# I2CRJ45X8.net
KiCad netlist of a schematic drawn in EAGLE
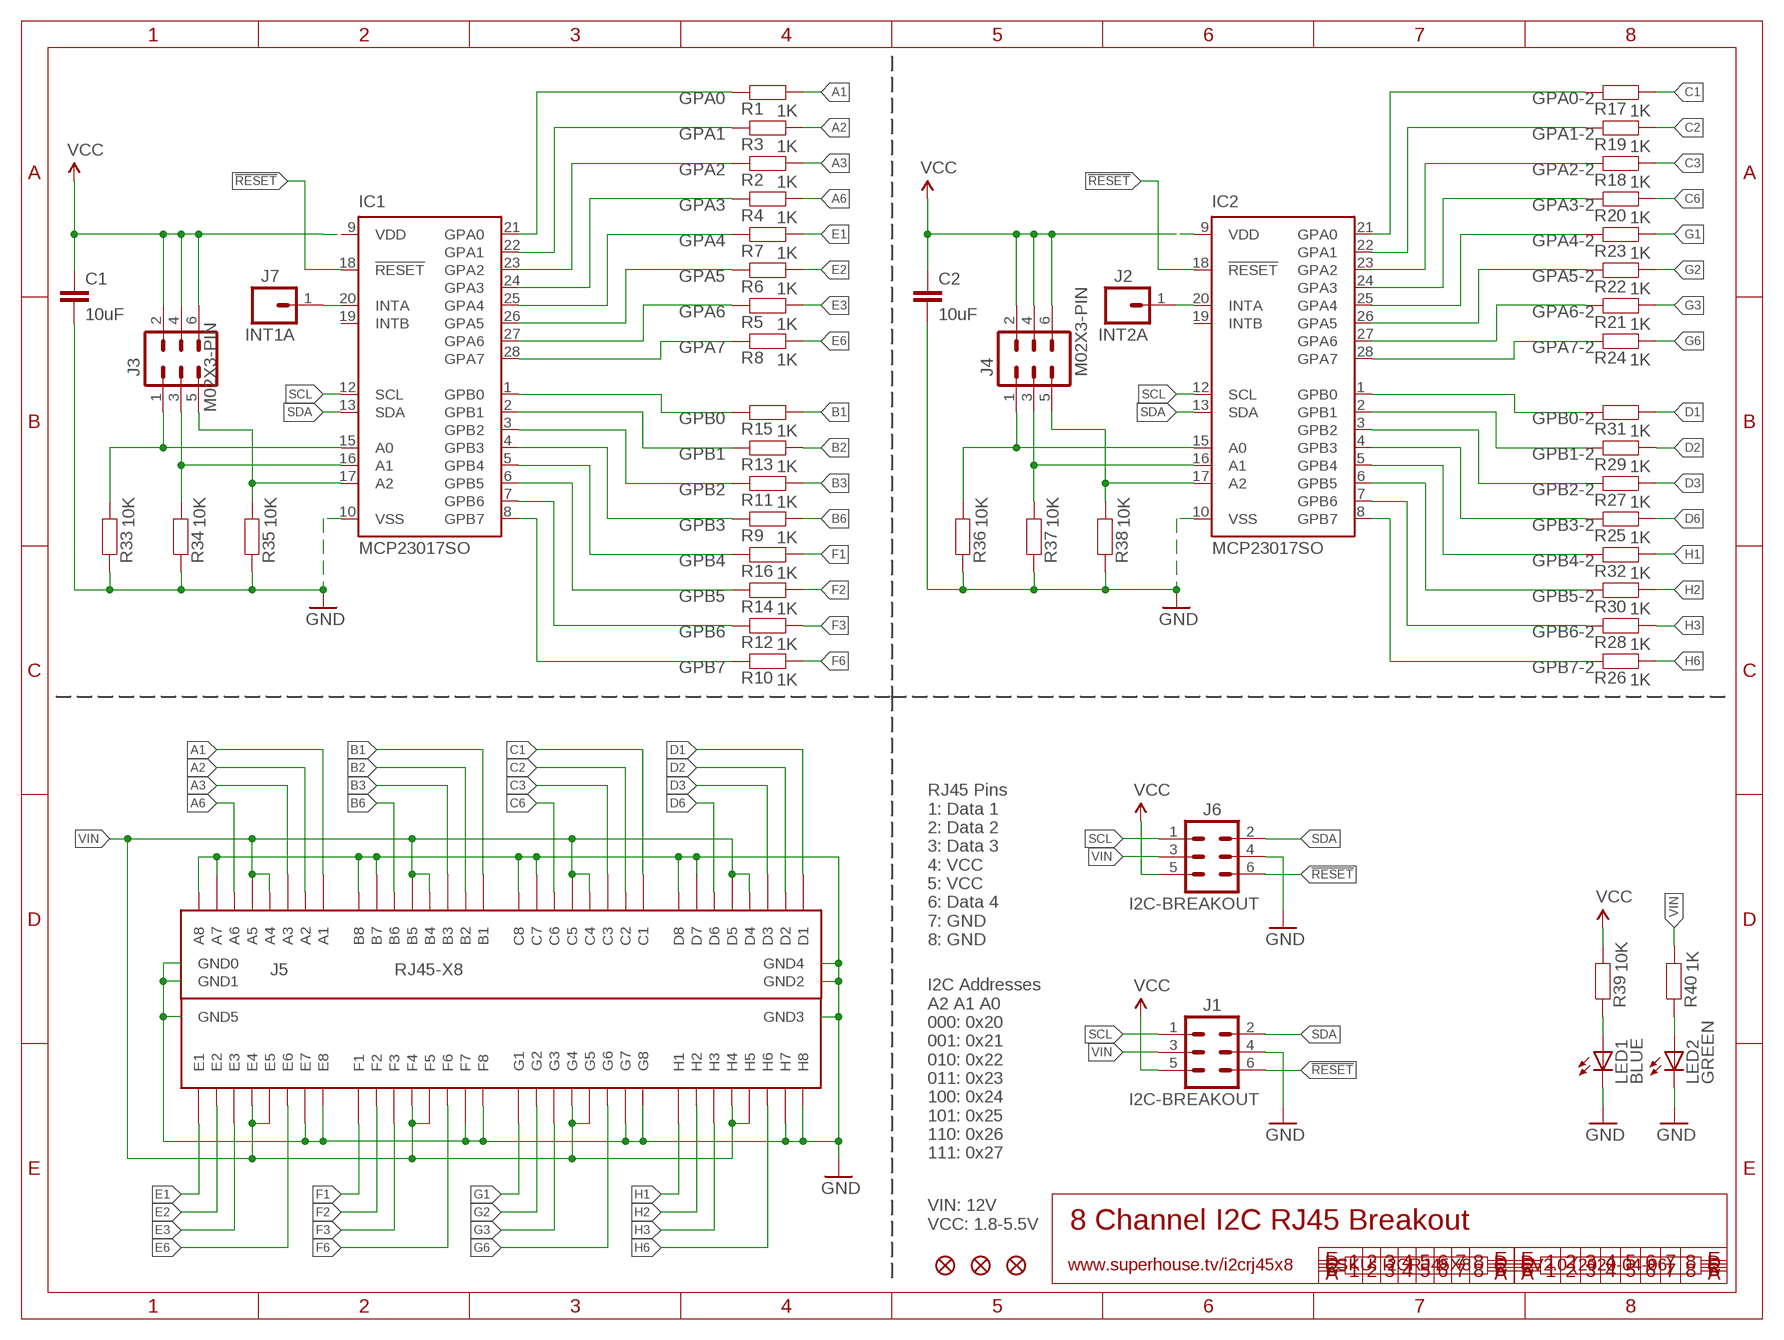
[diagram p0: schematic, sheet 1]

(export (version "E")
  (design (tool "Eeschema 10.0.6"))
  (components
    (comp (ref "C1")
      (value "10uF")
      (footprint "eagle-import:C0805")
      (libsource (lib "eagle-import") (part "CAP0805"))
    )
    (comp (ref "C2")
      (value "10uF")
      (footprint "eagle-import:C0805")
      (libsource (lib "eagle-import") (part "CAP0805"))
    )
    (comp (ref "FID1")
      (value "FIDUCIAL1X2.5")
      (footprint "eagle-import:FIDUCIAL-1X2.5")
      (libsource (lib "eagle-import") (part "FIDUCIAL1X2.5"))
    )
    (comp (ref "FID2")
      (value "FIDUCIAL1X2.5")
      (footprint "eagle-import:FIDUCIAL-1X2.5")
      (libsource (lib "eagle-import") (part "FIDUCIAL1X2.5"))
    )
    (comp (ref "FID3")
      (value "FIDUCIAL1X2.5")
      (footprint "eagle-import:FIDUCIAL-1X2.5")
      (libsource (lib "eagle-import") (part "FIDUCIAL1X2.5"))
    )
    (comp (ref "IC1")
      (value "MCP23017SO")
      (footprint "eagle-import:SO28W")
      (libsource (lib "eagle-import") (part "MCP23017SO"))
    )
    (comp (ref "IC2")
      (value "MCP23017SO")
      (footprint "eagle-import:SO28W")
      (libsource (lib "eagle-import") (part "MCP23017SO"))
    )
    (comp (ref "J1")
      (value "I2C-BREAKOUT")
      (footprint "eagle-import:2X03-SHROUDED")
      (libsource (lib "eagle-import") (part "M02X3-SHROUDED"))
    )
    (comp (ref "J2")
      (value "INT2A")
      (footprint "eagle-import:1X01")
      (libsource (lib "eagle-import") (part "M01-PLAIN"))
    )
    (comp (ref "J3")
      (value "M02X3-PIN")
      (footprint "eagle-import:2X03-P")
      (libsource (lib "eagle-import") (part "M02X3-PIN"))
    )
    (comp (ref "J4")
      (value "M02X3-PIN")
      (footprint "eagle-import:2X03-P")
      (libsource (lib "eagle-import") (part "M02X3-PIN"))
    )
    (comp (ref "J5")
      (value "RJ45-X8")
      (footprint "eagle-import:RJ45-2X4")
      (libsource (lib "eagle-import") (part "RJ45-X8"))
    )
    (comp (ref "J6")
      (value "I2C-BREAKOUT")
      (footprint "eagle-import:2X03-SHROUDED")
      (libsource (lib "eagle-import") (part "M02X3-SHROUDED"))
    )
    (comp (ref "J7")
      (value "INT1A")
      (footprint "eagle-import:1X01")
      (libsource (lib "eagle-import") (part "M01-PLAIN"))
    )
    (comp (ref "LED1")
      (value "BLUE")
      (footprint "eagle-import:LED-0603")
      (libsource (lib "eagle-import") (part "LED0603"))
    )
    (comp (ref "LED2")
      (value "GREEN")
      (footprint "eagle-import:LED-0603")
      (libsource (lib "eagle-import") (part "LED0603"))
    )
    (comp (ref "R1")
      (value "1K")
      (footprint "eagle-import:R0603")
      (libsource (lib "eagle-import") (part "RESISTOR0603"))
    )
    (comp (ref "R2")
      (value "1K")
      (footprint "eagle-import:R0603")
      (libsource (lib "eagle-import") (part "RESISTOR0603"))
    )
    (comp (ref "R3")
      (value "1K")
      (footprint "eagle-import:R0603")
      (libsource (lib "eagle-import") (part "RESISTOR0603"))
    )
    (comp (ref "R4")
      (value "1K")
      (footprint "eagle-import:R0603")
      (libsource (lib "eagle-import") (part "RESISTOR0603"))
    )
    (comp (ref "R5")
      (value "1K")
      (footprint "eagle-import:R0603")
      (libsource (lib "eagle-import") (part "RESISTOR0603"))
    )
    (comp (ref "R6")
      (value "1K")
      (footprint "eagle-import:R0603")
      (libsource (lib "eagle-import") (part "RESISTOR0603"))
    )
    (comp (ref "R7")
      (value "1K")
      (footprint "eagle-import:R0603")
      (libsource (lib "eagle-import") (part "RESISTOR0603"))
    )
    (comp (ref "R8")
      (value "1K")
      (footprint "eagle-import:R0603")
      (libsource (lib "eagle-import") (part "RESISTOR0603"))
    )
    (comp (ref "R9")
      (value "1K")
      (footprint "eagle-import:R0603")
      (libsource (lib "eagle-import") (part "RESISTOR0603"))
    )
    (comp (ref "R10")
      (value "1K")
      (footprint "eagle-import:R0603")
      (libsource (lib "eagle-import") (part "RESISTOR0603"))
    )
    (comp (ref "R11")
      (value "1K")
      (footprint "eagle-import:R0603")
      (libsource (lib "eagle-import") (part "RESISTOR0603"))
    )
    (comp (ref "R12")
      (value "1K")
      (footprint "eagle-import:R0603")
      (libsource (lib "eagle-import") (part "RESISTOR0603"))
    )
    (comp (ref "R13")
      (value "1K")
      (footprint "eagle-import:R0603")
      (libsource (lib "eagle-import") (part "RESISTOR0603"))
    )
    (comp (ref "R14")
      (value "1K")
      (footprint "eagle-import:R0603")
      (libsource (lib "eagle-import") (part "RESISTOR0603"))
    )
    (comp (ref "R15")
      (value "1K")
      (footprint "eagle-import:R0603")
      (libsource (lib "eagle-import") (part "RESISTOR0603"))
    )
    (comp (ref "R16")
      (value "1K")
      (footprint "eagle-import:R0603")
      (libsource (lib "eagle-import") (part "RESISTOR0603"))
    )
    (comp (ref "R17")
      (value "1K")
      (footprint "eagle-import:R0603")
      (libsource (lib "eagle-import") (part "RESISTOR0603"))
    )
    (comp (ref "R18")
      (value "1K")
      (footprint "eagle-import:R0603")
      (libsource (lib "eagle-import") (part "RESISTOR0603"))
    )
    (comp (ref "R19")
      (value "1K")
      (footprint "eagle-import:R0603")
      (libsource (lib "eagle-import") (part "RESISTOR0603"))
    )
    (comp (ref "R20")
      (value "1K")
      (footprint "eagle-import:R0603")
      (libsource (lib "eagle-import") (part "RESISTOR0603"))
    )
    (comp (ref "R21")
      (value "1K")
      (footprint "eagle-import:R0603")
      (libsource (lib "eagle-import") (part "RESISTOR0603"))
    )
    (comp (ref "R22")
      (value "1K")
      (footprint "eagle-import:R0603")
      (libsource (lib "eagle-import") (part "RESISTOR0603"))
    )
    (comp (ref "R23")
      (value "1K")
      (footprint "eagle-import:R0603")
      (libsource (lib "eagle-import") (part "RESISTOR0603"))
    )
    (comp (ref "R24")
      (value "1K")
      (footprint "eagle-import:R0603")
      (libsource (lib "eagle-import") (part "RESISTOR0603"))
    )
    (comp (ref "R25")
      (value "1K")
      (footprint "eagle-import:R0603")
      (libsource (lib "eagle-import") (part "RESISTOR0603"))
    )
    (comp (ref "R26")
      (value "1K")
      (footprint "eagle-import:R0603")
      (libsource (lib "eagle-import") (part "RESISTOR0603"))
    )
    (comp (ref "R27")
      (value "1K")
      (footprint "eagle-import:R0603")
      (libsource (lib "eagle-import") (part "RESISTOR0603"))
    )
    (comp (ref "R28")
      (value "1K")
      (footprint "eagle-import:R0603")
      (libsource (lib "eagle-import") (part "RESISTOR0603"))
    )
    (comp (ref "R29")
      (value "1K")
      (footprint "eagle-import:R0603")
      (libsource (lib "eagle-import") (part "RESISTOR0603"))
    )
    (comp (ref "R30")
      (value "1K")
      (footprint "eagle-import:R0603")
      (libsource (lib "eagle-import") (part "RESISTOR0603"))
    )
    (comp (ref "R31")
      (value "1K")
      (footprint "eagle-import:R0603")
      (libsource (lib "eagle-import") (part "RESISTOR0603"))
    )
    (comp (ref "R32")
      (value "1K")
      (footprint "eagle-import:R0603")
      (libsource (lib "eagle-import") (part "RESISTOR0603"))
    )
    (comp (ref "R33")
      (value "10K")
      (footprint "eagle-import:R0603")
      (libsource (lib "eagle-import") (part "RESISTOR0603"))
    )
    (comp (ref "R34")
      (value "10K")
      (footprint "eagle-import:R0603")
      (libsource (lib "eagle-import") (part "RESISTOR0603"))
    )
    (comp (ref "R35")
      (value "10K")
      (footprint "eagle-import:R0603")
      (libsource (lib "eagle-import") (part "RESISTOR0603"))
    )
    (comp (ref "R36")
      (value "10K")
      (footprint "eagle-import:R0603")
      (libsource (lib "eagle-import") (part "RESISTOR0603"))
    )
    (comp (ref "R37")
      (value "10K")
      (footprint "eagle-import:R0603")
      (libsource (lib "eagle-import") (part "RESISTOR0603"))
    )
    (comp (ref "R38")
      (value "10K")
      (footprint "eagle-import:R0603")
      (libsource (lib "eagle-import") (part "RESISTOR0603"))
    )
    (comp (ref "R39")
      (value "10K")
      (footprint "eagle-import:R0603")
      (libsource (lib "eagle-import") (part "RESISTOR0603"))
    )
    (comp (ref "R40")
      (value "1K")
      (footprint "eagle-import:R0603")
      (libsource (lib "eagle-import") (part "RESISTOR0603"))
    )
  )
  (nets
    (net (code "1") (name "/GPA0") (class "Default")
      (node (ref "IC1") (pin "21") (pinfunction "GPA0_21") (pintype "bidirectional"))
      (node (ref "R1") (pin "1") (pinfunction "1_1") (pintype "passive"))
    )
    (net (code "2") (name "/GPA0-2") (class "Default")
      (node (ref "IC2") (pin "21") (pinfunction "GPA0_21") (pintype "bidirectional"))
      (node (ref "R17") (pin "1") (pinfunction "1_1") (pintype "passive"))
    )
    (net (code "3") (name "/GPA1") (class "Default")
      (node (ref "IC1") (pin "22") (pinfunction "GPA1_22") (pintype "bidirectional"))
      (node (ref "R3") (pin "1") (pinfunction "1_1") (pintype "passive"))
    )
    (net (code "4") (name "/GPA1-2") (class "Default")
      (node (ref "IC2") (pin "22") (pinfunction "GPA1_22") (pintype "bidirectional"))
      (node (ref "R19") (pin "1") (pinfunction "1_1") (pintype "passive"))
    )
    (net (code "5") (name "/GPA2") (class "Default")
      (node (ref "IC1") (pin "23") (pinfunction "GPA2_23") (pintype "bidirectional"))
      (node (ref "R2") (pin "1") (pinfunction "1_1") (pintype "passive"))
    )
    (net (code "6") (name "/GPA2-2") (class "Default")
      (node (ref "IC2") (pin "23") (pinfunction "GPA2_23") (pintype "bidirectional"))
      (node (ref "R18") (pin "1") (pinfunction "1_1") (pintype "passive"))
    )
    (net (code "7") (name "/GPA3") (class "Default")
      (node (ref "IC1") (pin "24") (pinfunction "GPA3_24") (pintype "bidirectional"))
      (node (ref "R4") (pin "1") (pinfunction "1_1") (pintype "passive"))
    )
    (net (code "8") (name "/GPA3-2") (class "Default")
      (node (ref "IC2") (pin "24") (pinfunction "GPA3_24") (pintype "bidirectional"))
      (node (ref "R20") (pin "1") (pinfunction "1_1") (pintype "passive"))
    )
    (net (code "9") (name "/GPA4") (class "Default")
      (node (ref "IC1") (pin "25") (pinfunction "GPA4_25") (pintype "bidirectional"))
      (node (ref "R7") (pin "1") (pinfunction "1_1") (pintype "passive"))
    )
    (net (code "10") (name "/GPA4-2") (class "Default")
      (node (ref "IC2") (pin "25") (pinfunction "GPA4_25") (pintype "bidirectional"))
      (node (ref "R23") (pin "1") (pinfunction "1_1") (pintype "passive"))
    )
    (net (code "11") (name "/GPA5") (class "Default")
      (node (ref "IC1") (pin "26") (pinfunction "GPA5_26") (pintype "bidirectional"))
      (node (ref "R6") (pin "1") (pinfunction "1_1") (pintype "passive"))
    )
    (net (code "12") (name "/GPA5-2") (class "Default")
      (node (ref "IC2") (pin "26") (pinfunction "GPA5_26") (pintype "bidirectional"))
      (node (ref "R22") (pin "1") (pinfunction "1_1") (pintype "passive"))
    )
    (net (code "13") (name "/GPA6") (class "Default")
      (node (ref "IC1") (pin "27") (pinfunction "GPA6_27") (pintype "bidirectional"))
      (node (ref "R5") (pin "1") (pinfunction "1_1") (pintype "passive"))
    )
    (net (code "14") (name "/GPA6-2") (class "Default")
      (node (ref "IC2") (pin "27") (pinfunction "GPA6_27") (pintype "bidirectional"))
      (node (ref "R21") (pin "1") (pinfunction "1_1") (pintype "passive"))
    )
    (net (code "15") (name "/GPA7") (class "Default")
      (node (ref "IC1") (pin "28") (pinfunction "GPA7_28") (pintype "bidirectional"))
      (node (ref "R8") (pin "1") (pinfunction "1_1") (pintype "passive"))
    )
    (net (code "16") (name "/GPA7-2") (class "Default")
      (node (ref "IC2") (pin "28") (pinfunction "GPA7_28") (pintype "bidirectional"))
      (node (ref "R24") (pin "1") (pinfunction "1_1") (pintype "passive"))
    )
    (net (code "17") (name "/GPB0") (class "Default")
      (node (ref "IC1") (pin "1") (pinfunction "GPB0_1") (pintype "bidirectional"))
      (node (ref "R15") (pin "1") (pinfunction "1_1") (pintype "passive"))
    )
    (net (code "18") (name "/GPB0-2") (class "Default")
      (node (ref "IC2") (pin "1") (pinfunction "GPB0_1") (pintype "bidirectional"))
      (node (ref "R31") (pin "1") (pinfunction "1_1") (pintype "passive"))
    )
    (net (code "19") (name "/GPB1") (class "Default")
      (node (ref "IC1") (pin "2") (pinfunction "GPB1_2") (pintype "bidirectional"))
      (node (ref "R13") (pin "1") (pinfunction "1_1") (pintype "passive"))
    )
    (net (code "20") (name "/GPB1-2") (class "Default")
      (node (ref "IC2") (pin "2") (pinfunction "GPB1_2") (pintype "bidirectional"))
      (node (ref "R29") (pin "1") (pinfunction "1_1") (pintype "passive"))
    )
    (net (code "21") (name "/GPB2") (class "Default")
      (node (ref "IC1") (pin "3") (pinfunction "GPB2_3") (pintype "bidirectional"))
      (node (ref "R11") (pin "1") (pinfunction "1_1") (pintype "passive"))
    )
    (net (code "22") (name "/GPB2-2") (class "Default")
      (node (ref "IC2") (pin "3") (pinfunction "GPB2_3") (pintype "bidirectional"))
      (node (ref "R27") (pin "1") (pinfunction "1_1") (pintype "passive"))
    )
    (net (code "23") (name "/GPB3") (class "Default")
      (node (ref "IC1") (pin "4") (pinfunction "GPB3_4") (pintype "bidirectional"))
      (node (ref "R9") (pin "1") (pinfunction "1_1") (pintype "passive"))
    )
    (net (code "24") (name "/GPB3-2") (class "Default")
      (node (ref "IC2") (pin "4") (pinfunction "GPB3_4") (pintype "bidirectional"))
      (node (ref "R25") (pin "1") (pinfunction "1_1") (pintype "passive"))
    )
    (net (code "25") (name "/GPB4") (class "Default")
      (node (ref "IC1") (pin "5") (pinfunction "GPB4_5") (pintype "bidirectional"))
      (node (ref "R16") (pin "1") (pinfunction "1_1") (pintype "passive"))
    )
    (net (code "26") (name "/GPB4-2") (class "Default")
      (node (ref "IC2") (pin "5") (pinfunction "GPB4_5") (pintype "bidirectional"))
      (node (ref "R32") (pin "1") (pinfunction "1_1") (pintype "passive"))
    )
    (net (code "27") (name "/GPB5") (class "Default")
      (node (ref "IC1") (pin "6") (pinfunction "GPB5_6") (pintype "bidirectional"))
      (node (ref "R14") (pin "1") (pinfunction "1_1") (pintype "passive"))
    )
    (net (code "28") (name "/GPB5-2") (class "Default")
      (node (ref "IC2") (pin "6") (pinfunction "GPB5_6") (pintype "bidirectional"))
      (node (ref "R30") (pin "1") (pinfunction "1_1") (pintype "passive"))
    )
    (net (code "29") (name "/GPB6") (class "Default")
      (node (ref "IC1") (pin "7") (pinfunction "GPB6_7") (pintype "bidirectional"))
      (node (ref "R12") (pin "1") (pinfunction "1_1") (pintype "passive"))
    )
    (net (code "30") (name "/GPB6-2") (class "Default")
      (node (ref "IC2") (pin "7") (pinfunction "GPB6_7") (pintype "bidirectional"))
      (node (ref "R28") (pin "1") (pinfunction "1_1") (pintype "passive"))
    )
    (net (code "31") (name "/GPB7") (class "Default")
      (node (ref "IC1") (pin "8") (pinfunction "GPB7_8") (pintype "bidirectional"))
      (node (ref "R10") (pin "1") (pinfunction "1_1") (pintype "passive"))
    )
    (net (code "32") (name "/GPB7-2") (class "Default")
      (node (ref "IC2") (pin "8") (pinfunction "GPB7_8") (pintype "bidirectional"))
      (node (ref "R26") (pin "1") (pinfunction "1_1") (pintype "passive"))
    )
    (net (code "33") (name "/~{RESET}") (class "Default")
      (node (ref "IC1") (pin "18") (pinfunction "~{RESET}_18") (pintype "input"))
      (node (ref "IC2") (pin "18") (pinfunction "~{RESET}_18") (pintype "input"))
      (node (ref "J1") (pin "6") (pinfunction "6_6") (pintype "passive"))
      (node (ref "J6") (pin "6") (pinfunction "6_6") (pintype "passive"))
    )
    (net (code "34") (name "A1") (class "Default")
      (node (ref "J5") (pin "A1") (pinfunction "A1_A1") (pintype "bidirectional"))
      (node (ref "R1") (pin "2") (pinfunction "2_2") (pintype "passive"))
    )
    (net (code "35") (name "A2") (class "Default")
      (node (ref "J5") (pin "A2") (pinfunction "A2_A2") (pintype "bidirectional"))
      (node (ref "R3") (pin "2") (pinfunction "2_2") (pintype "passive"))
    )
    (net (code "36") (name "A3") (class "Default")
      (node (ref "J5") (pin "A3") (pinfunction "A3_A3") (pintype "bidirectional"))
      (node (ref "R2") (pin "2") (pinfunction "2_2") (pintype "passive"))
    )
    (net (code "37") (name "A6") (class "Default")
      (node (ref "J5") (pin "A6") (pinfunction "A6_A6") (pintype "bidirectional"))
      (node (ref "R4") (pin "2") (pinfunction "2_2") (pintype "passive"))
    )
    (net (code "38") (name "B1") (class "Default")
      (node (ref "J5") (pin "B1") (pinfunction "B1_B1") (pintype "bidirectional"))
      (node (ref "R15") (pin "2") (pinfunction "2_2") (pintype "passive"))
    )
    (net (code "39") (name "B2") (class "Default")
      (node (ref "J5") (pin "B2") (pinfunction "B2_B2") (pintype "bidirectional"))
      (node (ref "R13") (pin "2") (pinfunction "2_2") (pintype "passive"))
    )
    (net (code "40") (name "B3") (class "Default")
      (node (ref "J5") (pin "B3") (pinfunction "B3_B3") (pintype "bidirectional"))
      (node (ref "R11") (pin "2") (pinfunction "2_2") (pintype "passive"))
    )
    (net (code "41") (name "B6") (class "Default")
      (node (ref "J5") (pin "B6") (pinfunction "B6_B6") (pintype "bidirectional"))
      (node (ref "R9") (pin "2") (pinfunction "2_2") (pintype "passive"))
    )
    (net (code "42") (name "C1") (class "Default")
      (node (ref "J5") (pin "C1") (pinfunction "C1_C1") (pintype "bidirectional"))
      (node (ref "R17") (pin "2") (pinfunction "2_2") (pintype "passive"))
    )
    (net (code "43") (name "C2") (class "Default")
      (node (ref "J5") (pin "C2") (pinfunction "C2_C2") (pintype "bidirectional"))
      (node (ref "R19") (pin "2") (pinfunction "2_2") (pintype "passive"))
    )
    (net (code "44") (name "C3") (class "Default")
      (node (ref "J5") (pin "C3") (pinfunction "C3_C3") (pintype "bidirectional"))
      (node (ref "R18") (pin "2") (pinfunction "2_2") (pintype "passive"))
    )
    (net (code "45") (name "C6") (class "Default")
      (node (ref "J5") (pin "C6") (pinfunction "C6_C6") (pintype "bidirectional"))
      (node (ref "R20") (pin "2") (pinfunction "2_2") (pintype "passive"))
    )
    (net (code "46") (name "D1") (class "Default")
      (node (ref "J5") (pin "D1") (pinfunction "D1_D1") (pintype "bidirectional"))
      (node (ref "R31") (pin "2") (pinfunction "2_2") (pintype "passive"))
    )
    (net (code "47") (name "D2") (class "Default")
      (node (ref "J5") (pin "D2") (pinfunction "D2_D2") (pintype "bidirectional"))
      (node (ref "R29") (pin "2") (pinfunction "2_2") (pintype "passive"))
    )
    (net (code "48") (name "D3") (class "Default")
      (node (ref "J5") (pin "D3") (pinfunction "D3_D3") (pintype "bidirectional"))
      (node (ref "R27") (pin "2") (pinfunction "2_2") (pintype "passive"))
    )
    (net (code "49") (name "D6") (class "Default")
      (node (ref "J5") (pin "D6") (pinfunction "D6_D6") (pintype "bidirectional"))
      (node (ref "R25") (pin "2") (pinfunction "2_2") (pintype "passive"))
    )
    (net (code "50") (name "E1") (class "Default")
      (node (ref "J5") (pin "E1") (pinfunction "E1_E1") (pintype "bidirectional"))
      (node (ref "R7") (pin "2") (pinfunction "2_2") (pintype "passive"))
    )
    (net (code "51") (name "E2") (class "Default")
      (node (ref "J5") (pin "E2") (pinfunction "E2_E2") (pintype "bidirectional"))
      (node (ref "R6") (pin "2") (pinfunction "2_2") (pintype "passive"))
    )
    (net (code "52") (name "E3") (class "Default")
      (node (ref "J5") (pin "E3") (pinfunction "E3_E3") (pintype "bidirectional"))
      (node (ref "R5") (pin "2") (pinfunction "2_2") (pintype "passive"))
    )
    (net (code "53") (name "E6") (class "Default")
      (node (ref "J5") (pin "E6") (pinfunction "E6_E6") (pintype "bidirectional"))
      (node (ref "R8") (pin "2") (pinfunction "2_2") (pintype "passive"))
    )
    (net (code "54") (name "F1") (class "Default")
      (node (ref "J5") (pin "F1") (pinfunction "F1_F1") (pintype "bidirectional"))
      (node (ref "R16") (pin "2") (pinfunction "2_2") (pintype "passive"))
    )
    (net (code "55") (name "F2") (class "Default")
      (node (ref "J5") (pin "F2") (pinfunction "F2_F2") (pintype "bidirectional"))
      (node (ref "R14") (pin "2") (pinfunction "2_2") (pintype "passive"))
    )
    (net (code "56") (name "F3") (class "Default")
      (node (ref "J5") (pin "F3") (pinfunction "F3_F3") (pintype "bidirectional"))
      (node (ref "R12") (pin "2") (pinfunction "2_2") (pintype "passive"))
    )
    (net (code "57") (name "F6") (class "Default")
      (node (ref "J5") (pin "F6") (pinfunction "F6_F6") (pintype "bidirectional"))
      (node (ref "R10") (pin "2") (pinfunction "2_2") (pintype "passive"))
    )
    (net (code "58") (name "G1") (class "Default")
      (node (ref "J5") (pin "G1") (pinfunction "G1_G1") (pintype "bidirectional"))
      (node (ref "R23") (pin "2") (pinfunction "2_2") (pintype "passive"))
    )
    (net (code "59") (name "G2") (class "Default")
      (node (ref "J5") (pin "G2") (pinfunction "G2_G2") (pintype "bidirectional"))
      (node (ref "R22") (pin "2") (pinfunction "2_2") (pintype "passive"))
    )
    (net (code "60") (name "G3") (class "Default")
      (node (ref "J5") (pin "G3") (pinfunction "G3_G3") (pintype "bidirectional"))
      (node (ref "R21") (pin "2") (pinfunction "2_2") (pintype "passive"))
    )
    (net (code "61") (name "G6") (class "Default")
      (node (ref "J5") (pin "G6") (pinfunction "G6_G6") (pintype "bidirectional"))
      (node (ref "R24") (pin "2") (pinfunction "2_2") (pintype "passive"))
    )
    (net (code "62") (name "GND") (class "Default")
      (node (ref "C1") (pin "2") (pinfunction "2_2") (pintype "passive"))
      (node (ref "C2") (pin "2") (pinfunction "2_2") (pintype "passive"))
      (node (ref "IC1") (pin "10") (pinfunction "VSS_10") (pintype "power_in"))
      (node (ref "IC2") (pin "10") (pinfunction "VSS_10") (pintype "power_in"))
      (node (ref "J1") (pin "4") (pinfunction "4_4") (pintype "passive"))
      (node (ref "J5") (pin "A7") (pinfunction "A7_A7") (pintype "bidirectional"))
      (node (ref "J5") (pin "A8") (pinfunction "A8_A8") (pintype "bidirectional"))
      (node (ref "J5") (pin "B7") (pinfunction "B7_B7") (pintype "bidirectional"))
      (node (ref "J5") (pin "B8") (pinfunction "B8_B8") (pintype "bidirectional"))
      (node (ref "J5") (pin "C7") (pinfunction "C7_C7") (pintype "bidirectional"))
      (node (ref "J5") (pin "C8") (pinfunction "C8_C8") (pintype "bidirectional"))
      (node (ref "J5") (pin "D7") (pinfunction "D7_D7") (pintype "bidirectional"))
      (node (ref "J5") (pin "D8") (pinfunction "D8_D8") (pintype "bidirectional"))
      (node (ref "J5") (pin "E7") (pinfunction "E7_E7") (pintype "bidirectional"))
      (node (ref "J5") (pin "E8") (pinfunction "E8_E8") (pintype "bidirectional"))
      (node (ref "J5") (pin "F7") (pinfunction "F7_F7") (pintype "bidirectional"))
      (node (ref "J5") (pin "F8") (pinfunction "F8_F8") (pintype "bidirectional"))
      (node (ref "J5") (pin "G7") (pinfunction "G7_G7") (pintype "bidirectional"))
      (node (ref "J5") (pin "G8") (pinfunction "G8_G8") (pintype "bidirectional"))
      (node (ref "J5") (pin "GND0") (pinfunction "GND0_GND0") (pintype "power_in"))
      (node (ref "J5") (pin "GND1") (pinfunction "GND1_GND1") (pintype "power_in"))
      (node (ref "J5") (pin "GND2") (pinfunction "GND2_GND2") (pintype "power_in"))
      (node (ref "J5") (pin "GND3") (pinfunction "GND3_GND3") (pintype "power_in"))
      (node (ref "J5") (pin "GND4") (pinfunction "GND4_GND4") (pintype "power_in"))
      (node (ref "J5") (pin "GND5") (pinfunction "GND5_GND5") (pintype "power_in"))
      (node (ref "J5") (pin "H7") (pinfunction "H7_H7") (pintype "bidirectional"))
      (node (ref "J5") (pin "H8") (pinfunction "H8_H8") (pintype "bidirectional"))
      (node (ref "J6") (pin "4") (pinfunction "4_4") (pintype "passive"))
      (node (ref "LED1") (pin "C") (pinfunction "C_C") (pintype "passive"))
      (node (ref "LED2") (pin "C") (pinfunction "C_C") (pintype "passive"))
      (node (ref "R33") (pin "1") (pinfunction "1_1") (pintype "passive"))
      (node (ref "R34") (pin "1") (pinfunction "1_1") (pintype "passive"))
      (node (ref "R35") (pin "1") (pinfunction "1_1") (pintype "passive"))
      (node (ref "R36") (pin "1") (pinfunction "1_1") (pintype "passive"))
      (node (ref "R37") (pin "1") (pinfunction "1_1") (pintype "passive"))
      (node (ref "R38") (pin "1") (pinfunction "1_1") (pintype "passive"))
    )
    (net (code "63") (name "H1") (class "Default")
      (node (ref "J5") (pin "H1") (pinfunction "H1_H1") (pintype "bidirectional"))
      (node (ref "R32") (pin "2") (pinfunction "2_2") (pintype "passive"))
    )
    (net (code "64") (name "H2") (class "Default")
      (node (ref "J5") (pin "H2") (pinfunction "H2_H2") (pintype "bidirectional"))
      (node (ref "R30") (pin "2") (pinfunction "2_2") (pintype "passive"))
    )
    (net (code "65") (name "H3") (class "Default")
      (node (ref "J5") (pin "H3") (pinfunction "H3_H3") (pintype "bidirectional"))
      (node (ref "R28") (pin "2") (pinfunction "2_2") (pintype "passive"))
    )
    (net (code "66") (name "H6") (class "Default")
      (node (ref "J5") (pin "H6") (pinfunction "H6_H6") (pintype "bidirectional"))
      (node (ref "R26") (pin "2") (pinfunction "2_2") (pintype "passive"))
    )
    (net (code "67") (name "Net-(IC1-A0)") (class "Default")
      (node (ref "IC1") (pin "15") (pinfunction "A0_15") (pintype "input"))
      (node (ref "J3") (pin "1") (pinfunction "1_1") (pintype "passive"))
      (node (ref "R33") (pin "2") (pinfunction "2_2") (pintype "passive"))
    )
    (net (code "68") (name "Net-(IC1-A1)") (class "Default")
      (node (ref "IC1") (pin "16") (pinfunction "A1_16") (pintype "input"))
      (node (ref "J3") (pin "3") (pinfunction "3_3") (pintype "passive"))
      (node (ref "R34") (pin "2") (pinfunction "2_2") (pintype "passive"))
    )
    (net (code "69") (name "Net-(IC1-A2)") (class "Default")
      (node (ref "IC1") (pin "17") (pinfunction "A2_17") (pintype "input"))
      (node (ref "J3") (pin "5") (pinfunction "5_5") (pintype "passive"))
      (node (ref "R35") (pin "2") (pinfunction "2_2") (pintype "passive"))
    )
    (net (code "70") (name "Net-(IC1-INTA)") (class "Default")
      (node (ref "IC1") (pin "20") (pinfunction "INTA_20") (pintype "output"))
      (node (ref "J7") (pin "1") (pinfunction "1_1") (pintype "passive"))
    )
    (net (code "71") (name "Net-(IC2-A0)") (class "Default")
      (node (ref "IC2") (pin "15") (pinfunction "A0_15") (pintype "input"))
      (node (ref "J4") (pin "1") (pinfunction "1_1") (pintype "passive"))
      (node (ref "R36") (pin "2") (pinfunction "2_2") (pintype "passive"))
    )
    (net (code "72") (name "Net-(IC2-A1)") (class "Default")
      (node (ref "IC2") (pin "16") (pinfunction "A1_16") (pintype "input"))
      (node (ref "J4") (pin "3") (pinfunction "3_3") (pintype "passive"))
      (node (ref "R37") (pin "2") (pinfunction "2_2") (pintype "passive"))
    )
    (net (code "73") (name "Net-(IC2-A2)") (class "Default")
      (node (ref "IC2") (pin "17") (pinfunction "A2_17") (pintype "input"))
      (node (ref "J4") (pin "5") (pinfunction "5_5") (pintype "passive"))
      (node (ref "R38") (pin "2") (pinfunction "2_2") (pintype "passive"))
    )
    (net (code "74") (name "Net-(IC2-INTA)") (class "Default")
      (node (ref "IC2") (pin "20") (pinfunction "INTA_20") (pintype "output"))
      (node (ref "J2") (pin "1") (pinfunction "1_1") (pintype "passive"))
    )
    (net (code "75") (name "Net-(LED1-PadA)") (class "Default")
      (node (ref "LED1") (pin "A") (pinfunction "A_A") (pintype "passive"))
      (node (ref "R39") (pin "1") (pinfunction "1_1") (pintype "passive"))
    )
    (net (code "76") (name "Net-(LED2-PadA)") (class "Default")
      (node (ref "LED2") (pin "A") (pinfunction "A_A") (pintype "passive"))
      (node (ref "R40") (pin "1") (pinfunction "1_1") (pintype "passive"))
    )
    (net (code "77") (name "SCL") (class "Default")
      (node (ref "IC1") (pin "12") (pinfunction "SCL_12") (pintype "input"))
      (node (ref "IC2") (pin "12") (pinfunction "SCL_12") (pintype "input"))
      (node (ref "J1") (pin "1") (pinfunction "1_1") (pintype "passive"))
      (node (ref "J6") (pin "1") (pinfunction "1_1") (pintype "passive"))
    )
    (net (code "78") (name "SDA") (class "Default")
      (node (ref "IC1") (pin "13") (pinfunction "SDA_13") (pintype "bidirectional"))
      (node (ref "IC2") (pin "13") (pinfunction "SDA_13") (pintype "bidirectional"))
      (node (ref "J1") (pin "2") (pinfunction "2_2") (pintype "passive"))
      (node (ref "J6") (pin "2") (pinfunction "2_2") (pintype "passive"))
    )
    (net (code "79") (name "VCC") (class "Default")
      (node (ref "C1") (pin "1") (pinfunction "1_1") (pintype "passive"))
      (node (ref "C2") (pin "1") (pinfunction "1_1") (pintype "passive"))
      (node (ref "IC1") (pin "9") (pinfunction "VDD_9") (pintype "power_in"))
      (node (ref "IC2") (pin "9") (pinfunction "VDD_9") (pintype "power_in"))
      (node (ref "J1") (pin "5") (pinfunction "5_5") (pintype "passive"))
      (node (ref "J3") (pin "2") (pinfunction "2_2") (pintype "passive"))
      (node (ref "J3") (pin "4") (pinfunction "4_4") (pintype "passive"))
      (node (ref "J3") (pin "6") (pinfunction "6_6") (pintype "passive"))
      (node (ref "J4") (pin "2") (pinfunction "2_2") (pintype "passive"))
      (node (ref "J4") (pin "4") (pinfunction "4_4") (pintype "passive"))
      (node (ref "J4") (pin "6") (pinfunction "6_6") (pintype "passive"))
      (node (ref "J6") (pin "5") (pinfunction "5_5") (pintype "passive"))
      (node (ref "R39") (pin "2") (pinfunction "2_2") (pintype "passive"))
    )
    (net (code "80") (name "VIN") (class "Default")
      (node (ref "J1") (pin "3") (pinfunction "3_3") (pintype "passive"))
      (node (ref "J5") (pin "A4") (pinfunction "A4_A4") (pintype "bidirectional"))
      (node (ref "J5") (pin "A5") (pinfunction "A5_A5") (pintype "bidirectional"))
      (node (ref "J5") (pin "B4") (pinfunction "B4_B4") (pintype "bidirectional"))
      (node (ref "J5") (pin "B5") (pinfunction "B5_B5") (pintype "bidirectional"))
      (node (ref "J5") (pin "C4") (pinfunction "C4_C4") (pintype "bidirectional"))
      (node (ref "J5") (pin "C5") (pinfunction "C5_C5") (pintype "bidirectional"))
      (node (ref "J5") (pin "D4") (pinfunction "D4_D4") (pintype "bidirectional"))
      (node (ref "J5") (pin "D5") (pinfunction "D5_D5") (pintype "bidirectional"))
      (node (ref "J5") (pin "E4") (pinfunction "E4_E4") (pintype "bidirectional"))
      (node (ref "J5") (pin "E5") (pinfunction "E5_E5") (pintype "bidirectional"))
      (node (ref "J5") (pin "F4") (pinfunction "F4_F4") (pintype "bidirectional"))
      (node (ref "J5") (pin "F5") (pinfunction "F5_F5") (pintype "bidirectional"))
      (node (ref "J5") (pin "G4") (pinfunction "G4_G4") (pintype "bidirectional"))
      (node (ref "J5") (pin "G5") (pinfunction "G5_G5") (pintype "bidirectional"))
      (node (ref "J5") (pin "H4") (pinfunction "H4_H4") (pintype "bidirectional"))
      (node (ref "J5") (pin "H5") (pinfunction "H5_H5") (pintype "bidirectional"))
      (node (ref "J6") (pin "3") (pinfunction "3_3") (pintype "passive"))
      (node (ref "R40") (pin "2") (pinfunction "2_2") (pintype "passive"))
    )
    (net (code "81") (name "unconnected-(IC1-INTB-Pad19)") (class "Default")
      (node (ref "IC1") (pin "19") (pinfunction "INTB_19") (pintype "output"))
    )
    (net (code "82") (name "unconnected-(IC2-INTB-Pad19)") (class "Default")
      (node (ref "IC2") (pin "19") (pinfunction "INTB_19") (pintype "output"))
    )
  )
)
